# IoT_Greenhouse_V1_0_A_-_Inputs.net
KiCad netlist of a schematic drawn in Altium Designer
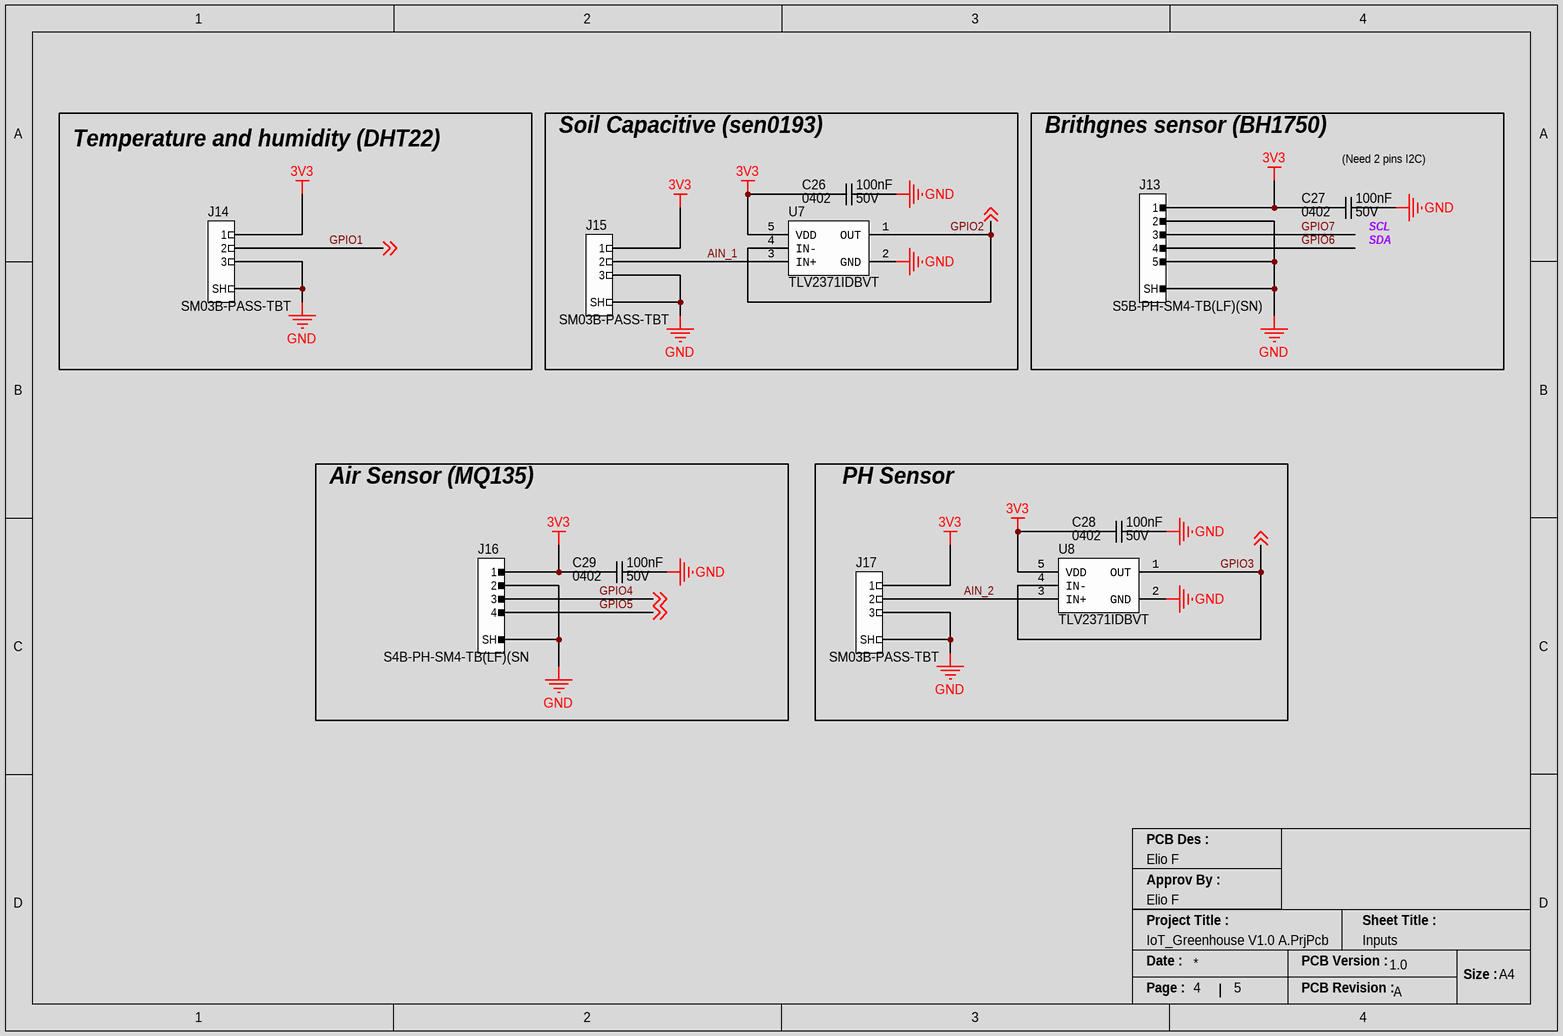
[diagram p0: IoT_Greenhouse V1.0 A - Inputs.SchDoc]

(export (version "E")
  (design (tool "Eeschema 10.0.6"))
  (components
    (comp (ref "C26")
      (value "GRM155R71H104KE14D")
      (footprint "CAP_0402_CAPC1005X05N")
      (description "Multilayer Ceramic Capacitor, 0.1 uF, 16 V, ± 10%, X7R, 0402 [1005 Metric]")
      (fields
        (field (name "MANUFACTURER") "Murata")
        (field (name "TOLERANCE") "10%")
        (field (name "VOLTAGE RATING") "50V")
        (field (name "CAPACITANCE") "100nF")
        (field (name "CASE/PACKAGE") "0402")
      )
      (libsource (lib "Electronic Devices_LIB") (part "CAP_100NF_50V_X7R_0402"))
    )
    (comp (ref "C27")
      (value "GRM155R71H104KE14D")
      (footprint "CAP_0402_CAPC1005X05N")
      (description "Multilayer Ceramic Capacitor, 0.1 uF, 16 V, ± 10%, X7R, 0402 [1005 Metric]")
      (fields
        (field (name "MANUFACTURER") "Murata")
        (field (name "TOLERANCE") "10%")
        (field (name "VOLTAGE RATING") "50V")
        (field (name "CAPACITANCE") "100nF")
        (field (name "CASE/PACKAGE") "0402")
      )
      (libsource (lib "Electronic Devices_LIB") (part "CAP_100NF_50V_X7R_0402"))
    )
    (comp (ref "C28")
      (value "GRM155R71H104KE14D")
      (footprint "CAP_0402_CAPC1005X05N")
      (description "Multilayer Ceramic Capacitor, 0.1 uF, 16 V, ± 10%, X7R, 0402 [1005 Metric]")
      (fields
        (field (name "MANUFACTURER") "Murata")
        (field (name "TOLERANCE") "10%")
        (field (name "VOLTAGE RATING") "50V")
        (field (name "CAPACITANCE") "100nF")
        (field (name "CASE/PACKAGE") "0402")
      )
      (libsource (lib "Electronic Devices_LIB") (part "CAP_100NF_50V_X7R_0402"))
    )
    (comp (ref "C29")
      (value "GRM155R71H104KE14D")
      (footprint "CAP_0402_CAPC1005X05N")
      (description "Multilayer Ceramic Capacitor, 0.1 uF, 16 V, ± 10%, X7R, 0402 [1005 Metric]")
      (fields
        (field (name "MANUFACTURER") "Murata")
        (field (name "TOLERANCE") "10%")
        (field (name "VOLTAGE RATING") "50V")
        (field (name "CAPACITANCE") "100nF")
        (field (name "CASE/PACKAGE") "0402")
      )
      (libsource (lib "Electronic Devices_LIB") (part "CAP_100NF_50V_X7R_0402"))
    )
    (comp (ref "J13")
      (value "S5B-PH-SM4-TB(LF)(SN)")
      (footprint "CONN_JST_S5B-PH-SM4-TB_LF_SN_0")
      (description "Conn Shrouded Header (4 Sides) HDR 5 POS 2mm Solder RA SMD T/R")
      (fields (field (name "MANUFACTURER") "JST"))
      (libsource (lib "Electronic Devices_LIB") (part "CONN_JST_PH_RA_5P_2mm"))
    )
    (comp (ref "J14")
      (value "SM03B-PASS-TBT")
      (footprint "CONN_JST_SM03B-PASS-TBT_LF_SN_MFG")
      (description "Conn Header SMD R/a 3POS 2MM")
      (fields (field (name "MANUFACTURER") "JST"))
      (libsource (lib "Electronic Devices_LIB") (part "CONN_JST_PH_3P_2MM_SM03B-PASS-TBT"))
    )
    (comp (ref "J15")
      (value "SM03B-PASS-TBT")
      (footprint "CONN_JST_SM03B-PASS-TBT_LF_SN_MFG")
      (description "Conn Header SMD R/a 3POS 2MM")
      (fields (field (name "MANUFACTURER") "JST"))
      (libsource (lib "Electronic Devices_LIB") (part "CONN_JST_PH_3P_2MM_SM03B-PASS-TBT"))
    )
    (comp (ref "J16")
      (value "S4B-PH-SM4-TB(LF)(SN")
      (footprint "CONN_JST_S4B-PH-SM4-TB_LF_SN_0")
      (fields (field (name "MANUFACTURER") "JST") (field (name "JLCPCB PART NUMBER") "C265102"))
      (libsource (lib "Electronic Devices_LIB") (part "CONN_JST_PH_RA_4P_2mm_JLCPCB"))
    )
    (comp (ref "J17")
      (value "SM03B-PASS-TBT")
      (footprint "CONN_JST_SM03B-PASS-TBT_LF_SN_MFG")
      (description "Conn Header SMD R/a 3POS 2MM")
      (fields (field (name "MANUFACTURER") "JST"))
      (libsource (lib "Electronic Devices_LIB") (part "CONN_JST_PH_3P_2MM_SM03B-PASS-TBT"))
    )
    (comp (ref "U7")
      (value "TLV2371IDBVT")
      (footprint "IC_AMP_OP_SOT95P280X145-5N")
      (description "Single 550-uA/channel, 3MHz, RRIO op amp 5-SOT-23 -40 to 125")
      (fields (field (name "MANUFACTURER") "Texas Instruments"))
      (libsource (lib "Electronic Devices_LIB") (part "IC_AMP_OP_TLV2371IDBVT"))
    )
    (comp (ref "U8")
      (value "TLV2371IDBVT")
      (footprint "IC_AMP_OP_SOT95P280X145-5N")
      (description "Single 550-uA/channel, 3MHz, RRIO op amp 5-SOT-23 -40 to 125")
      (fields (field (name "MANUFACTURER") "Texas Instruments"))
      (libsource (lib "Electronic Devices_LIB") (part "IC_AMP_OP_TLV2371IDBVT"))
    )
  )
  (nets
    (net (code "1") (name "/AIN_1") (class "Default")
      (node (ref "J15") (pin "2") (pinfunction "2_2") (pintype "passive"))
      (node (ref "U7") (pin "3") (pinfunction "IN+_3") (pintype "passive"))
    )
    (net (code "2") (name "/AIN_2") (class "Default")
      (node (ref "J17") (pin "2") (pinfunction "2_2") (pintype "passive"))
      (node (ref "U8") (pin "3") (pinfunction "IN+_3") (pintype "passive"))
    )
    (net (code "3") (name "/GPIO1") (class "Default")
      (node (ref "J14") (pin "2") (pinfunction "2_2") (pintype "passive"))
      (node (ref "J16") (pin "3") (pinfunction "3_3") (pintype "passive"))
      (node (ref "J16") (pin "4") (pinfunction "4_4") (pintype "passive"))
      (node (ref "U7") (pin "1") (pinfunction "OUT_1") (pintype "passive"))
      (node (ref "U7") (pin "4") (pinfunction "IN-_4") (pintype "passive"))
      (node (ref "U8") (pin "1") (pinfunction "OUT_1") (pintype "passive"))
      (node (ref "U8") (pin "4") (pinfunction "IN-_4") (pintype "passive"))
    )
    (net (code "4") (name "/GPIO6") (class "Default")
      (node (ref "J13") (pin "4") (pinfunction "4_4") (pintype "passive"))
    )
    (net (code "5") (name "/GPIO7") (class "Default")
      (node (ref "J13") (pin "3") (pinfunction "3_3") (pintype "passive"))
    )
    (net (code "6") (name "3V3") (class "Default")
      (node (ref "C26") (pin "2") (pinfunction "2_2") (pintype "passive"))
      (node (ref "C27") (pin "2") (pinfunction "2_2") (pintype "passive"))
      (node (ref "C28") (pin "2") (pinfunction "2_2") (pintype "passive"))
      (node (ref "C29") (pin "2") (pinfunction "2_2") (pintype "passive"))
      (node (ref "J13") (pin "1") (pinfunction "1_1") (pintype "passive"))
      (node (ref "J14") (pin "1") (pinfunction "1_1") (pintype "passive"))
      (node (ref "J15") (pin "1") (pinfunction "1_1") (pintype "passive"))
      (node (ref "J16") (pin "1") (pinfunction "1_1") (pintype "passive"))
      (node (ref "J17") (pin "1") (pinfunction "1_1") (pintype "passive"))
      (node (ref "U7") (pin "5") (pinfunction "VDD_5") (pintype "power_in"))
      (node (ref "U8") (pin "5") (pinfunction "VDD_5") (pintype "power_in"))
    )
    (net (code "7") (name "GND") (class "Default")
      (node (ref "C26") (pin "1") (pinfunction "1_1") (pintype "passive"))
      (node (ref "C27") (pin "1") (pinfunction "1_1") (pintype "passive"))
      (node (ref "C28") (pin "1") (pinfunction "1_1") (pintype "passive"))
      (node (ref "C29") (pin "1") (pinfunction "1_1") (pintype "passive"))
      (node (ref "J13") (pin "0") (pinfunction "SH_0") (pintype "passive"))
      (node (ref "J13") (pin "2") (pinfunction "2_2") (pintype "passive"))
      (node (ref "J13") (pin "5") (pinfunction "5_5") (pintype "passive"))
      (node (ref "J14") (pin "3") (pinfunction "3_3") (pintype "passive"))
      (node (ref "J14") (pin "SH") (pinfunction "SH_SH") (pintype "passive"))
      (node (ref "J15") (pin "3") (pinfunction "3_3") (pintype "passive"))
      (node (ref "J15") (pin "SH") (pinfunction "SH_SH") (pintype "passive"))
      (node (ref "J16") (pin "0") (pinfunction "SH_0") (pintype "passive"))
      (node (ref "J16") (pin "2") (pinfunction "2_2") (pintype "passive"))
      (node (ref "J17") (pin "3") (pinfunction "3_3") (pintype "passive"))
      (node (ref "J17") (pin "SH") (pinfunction "SH_SH") (pintype "passive"))
      (node (ref "U7") (pin "2") (pinfunction "GND_2") (pintype "power_in"))
      (node (ref "U8") (pin "2") (pinfunction "GND_2") (pintype "power_in"))
    )
  )
)
